# PiGRRL_Zero_buttonpad.net
KiCad netlist of a schematic drawn in EAGLE
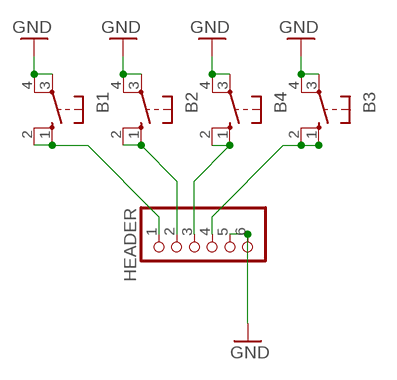
[diagram p0: schematic, sheet 1]

(export (version "E")
  (design (tool "Eeschema 10.0.6"))
  (components
    (comp (ref "B1")
      (value "10-XX")
      (footprint "eagle-import:B3F-10XX")
      (fields (field (name "MPN") "B3F-1000"))
      (libsource (lib "eagle-import") (part "10-XX"))
    )
    (comp (ref "B2")
      (value "10-XX")
      (footprint "eagle-import:B3F-10XX")
      (fields (field (name "MPN") "B3F-1000"))
      (libsource (lib "eagle-import") (part "10-XX"))
    )
    (comp (ref "B3")
      (value "10-XX")
      (footprint "eagle-import:B3F-10XX")
      (fields (field (name "MPN") "B3F-1000"))
      (libsource (lib "eagle-import") (part "10-XX"))
    )
    (comp (ref "B4")
      (value "10-XX")
      (footprint "eagle-import:B3F-10XX")
      (fields (field (name "MPN") "B3F-1000"))
      (libsource (lib "eagle-import") (part "10-XX"))
    )
    (comp (ref "HEADER")
      (value "PINHD-1X6")
      (footprint "eagle-import:1X06")
      (libsource (lib "eagle-import") (part "PINHD-1X6"))
    )
  )
  (nets
    (net (code "1") (name "GND") (class "Default")
      (node (ref "B1") (pin "3") (pinfunction "P_3") (pintype "passive"))
      (node (ref "B1") (pin "4") (pinfunction "P1_4") (pintype "passive"))
      (node (ref "B2") (pin "3") (pinfunction "P_3") (pintype "passive"))
      (node (ref "B2") (pin "4") (pinfunction "P1_4") (pintype "passive"))
      (node (ref "B3") (pin "3") (pinfunction "P_3") (pintype "passive"))
      (node (ref "B3") (pin "4") (pinfunction "P1_4") (pintype "passive"))
      (node (ref "B4") (pin "3") (pinfunction "P_3") (pintype "passive"))
      (node (ref "B4") (pin "4") (pinfunction "P1_4") (pintype "passive"))
      (node (ref "HEADER") (pin "5") (pinfunction "5_5") (pintype "passive"))
      (node (ref "HEADER") (pin "6") (pinfunction "6_6") (pintype "passive"))
    )
    (net (code "2") (name "Net-(B1-S)") (class "Default")
      (node (ref "B1") (pin "1") (pinfunction "S_1") (pintype "passive"))
      (node (ref "B1") (pin "2") (pinfunction "S1_2") (pintype "passive"))
      (node (ref "HEADER") (pin "1") (pinfunction "1_1") (pintype "passive"))
    )
    (net (code "3") (name "Net-(B2-S)") (class "Default")
      (node (ref "B2") (pin "1") (pinfunction "S_1") (pintype "passive"))
      (node (ref "B2") (pin "2") (pinfunction "S1_2") (pintype "passive"))
      (node (ref "HEADER") (pin "2") (pinfunction "2_2") (pintype "passive"))
    )
    (net (code "4") (name "Net-(B3-S)") (class "Default")
      (node (ref "B3") (pin "1") (pinfunction "S_1") (pintype "passive"))
      (node (ref "B3") (pin "2") (pinfunction "S1_2") (pintype "passive"))
      (node (ref "HEADER") (pin "4") (pinfunction "4_4") (pintype "passive"))
    )
    (net (code "5") (name "Net-(B4-S)") (class "Default")
      (node (ref "B4") (pin "1") (pinfunction "S_1") (pintype "passive"))
      (node (ref "B4") (pin "2") (pinfunction "S1_2") (pintype "passive"))
      (node (ref "HEADER") (pin "3") (pinfunction "3_3") (pintype "passive"))
    )
  )
)
